# 3d_printer_timer.net
KiCad netlist of a schematic drawn in EAGLE
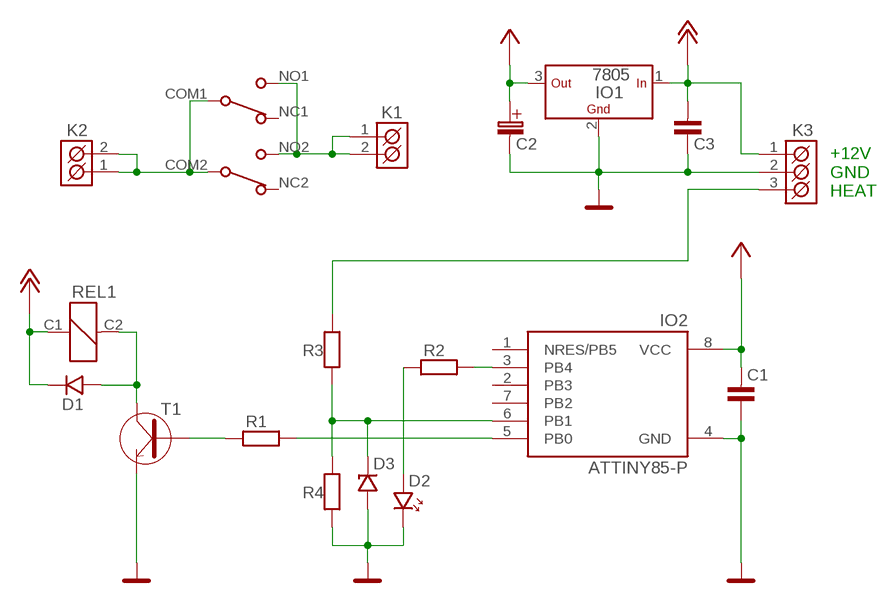
[diagram p0: schematic, sheet 1]

(export (version "E")
  (design (tool "Eeschema 10.0.6"))
  (components
    (comp (ref "C1")
      (value "100n")
      (footprint "eagle-import:1206")
      (libsource (lib "eagle-import") (part "C-KER_1206"))
    )
    (comp (ref "C2")
      (value "100u")
      (footprint "eagle-import:C-EL_2,5")
      (libsource (lib "eagle-import") (part "C-EL_2,5"))
    )
    (comp (ref "C3")
      (value "100n")
      (footprint "eagle-import:1206")
      (libsource (lib "eagle-import") (part "C-KER_1206"))
    )
    (comp (ref "D1")
      (value "1N4148")
      (footprint "eagle-import:DO35")
      (libsource (lib "eagle-import") (part "D_7,5"))
    )
    (comp (ref "D2")
      (value "LED_3")
      (footprint "eagle-import:LED_3")
      (libsource (lib "eagle-import") (part "LED_3"))
    )
    (comp (ref "D3")
      (value "5V1")
      (footprint "eagle-import:DO35")
      (libsource (lib "eagle-import") (part "D-?-ZENERBZX83V_0,5W"))
    )
    (comp (ref "IO1")
      (value "7805")
      (footprint "eagle-import:TO-220S")
      (libsource (lib "eagle-import") (part "78?_STO"))
    )
    (comp (ref "IO2")
      (value "ATTINY85-P")
      (footprint "eagle-import:PDIP08_300MIL")
      (libsource (lib "eagle-import") (part "ATTINY85P-"))
    )
    (comp (ref "K1")
      (value "ARK500/2")
      (footprint "eagle-import:ARK500_2")
      (libsource (lib "eagle-import") (part "ARK500/2"))
    )
    (comp (ref "K2")
      (value "ARK500/2")
      (footprint "eagle-import:ARK500_2")
      (libsource (lib "eagle-import") (part "ARK500/2"))
    )
    (comp (ref "K3")
      (value "ARK500/3")
      (footprint "eagle-import:ARK500_3")
      (libsource (lib "eagle-import") (part "ARK500/3"))
    )
    (comp (ref "R1")
      (value "1k")
      (footprint "eagle-import:R-10")
      (libsource (lib "eagle-import") (part "R_10"))
    )
    (comp (ref "R2")
      (value "330R")
      (footprint "eagle-import:R-10")
      (libsource (lib "eagle-import") (part "R_10"))
    )
    (comp (ref "R3")
      (value "R_10")
      (footprint "eagle-import:R-10")
      (libsource (lib "eagle-import") (part "R_10"))
    )
    (comp (ref "R4")
      (value "R_10")
      (footprint "eagle-import:R-10")
      (libsource (lib "eagle-import") (part "R_10"))
    )
    (comp (ref "REL1")
      (value "40.52")
      (footprint "eagle-import:RELEMZPA92")
      (libsource (lib "eagle-import") (part "RELEMZPA92"))
    )
    (comp (ref "T1")
      (value "BC546")
      (footprint "eagle-import:TO-92")
      (libsource (lib "eagle-import") (part "BC546"))
    )
  )
  (nets
    (net (code "1") (name "+5V") (class "Default")
      (node (ref "C1") (pin "2") (pinfunction "2_2") (pintype "passive"))
      (node (ref "C2") (pin "C+") (pinfunction "C_EL+_C+") (pintype "passive"))
      (node (ref "IO1") (pin "3") (pinfunction "OUT_3") (pintype "passive"))
      (node (ref "IO2") (pin "8") (pinfunction "VCC_8") (pintype "power_in"))
    )
    (net (code "2") (name "+12V") (class "Default")
      (node (ref "C3") (pin "2") (pinfunction "2_2") (pintype "passive"))
      (node (ref "D1") (pin "K") (pinfunction "K_K") (pintype "passive"))
      (node (ref "IO1") (pin "1") (pinfunction "IN_1") (pintype "passive"))
      (node (ref "K3") (pin "1") (pinfunction "K1_1") (pintype "passive"))
      (node (ref "REL1") (pin "C1") (pinfunction "C1_C1") (pintype "passive"))
    )
    (net (code "3") (name "GND") (class "Default")
      (node (ref "C1") (pin "1") (pinfunction "1_1") (pintype "passive"))
      (node (ref "C2") (pin "C-") (pinfunction "C_EL-_C-") (pintype "passive"))
      (node (ref "C3") (pin "1") (pinfunction "1_1") (pintype "passive"))
      (node (ref "D2") (pin "K") (pinfunction "K_K") (pintype "passive"))
      (node (ref "D3") (pin "A") (pinfunction "A_A") (pintype "passive"))
      (node (ref "IO1") (pin "2") (pinfunction "GND_2") (pintype "passive"))
      (node (ref "IO2") (pin "4") (pinfunction "GND_4") (pintype "power_in"))
      (node (ref "K3") (pin "2") (pinfunction "K2_2") (pintype "passive"))
      (node (ref "R4") (pin "1") (pinfunction "1_1") (pintype "passive"))
      (node (ref "T1") (pin "3") (pinfunction "E_3") (pintype "passive"))
    )
    (net (code "4") (name "Net-(D2-PadA)") (class "Default")
      (node (ref "D2") (pin "A") (pinfunction "A_A") (pintype "passive"))
      (node (ref "R2") (pin "1") (pinfunction "1_1") (pintype "passive"))
    )
    (net (code "5") (name "Net-(IO2-PB0)") (class "Default")
      (node (ref "IO2") (pin "5") (pinfunction "PB0_5") (pintype "bidirectional"))
      (node (ref "R1") (pin "2") (pinfunction "2_2") (pintype "passive"))
    )
    (net (code "6") (name "Net-(IO2-PB1)") (class "Default")
      (node (ref "D3") (pin "K") (pinfunction "K_K") (pintype "passive"))
      (node (ref "IO2") (pin "6") (pinfunction "PB1_6") (pintype "bidirectional"))
      (node (ref "R3") (pin "1") (pinfunction "1_1") (pintype "passive"))
      (node (ref "R4") (pin "2") (pinfunction "2_2") (pintype "passive"))
    )
    (net (code "7") (name "Net-(IO2-PB4)") (class "Default")
      (node (ref "IO2") (pin "3") (pinfunction "PB4_3") (pintype "bidirectional"))
      (node (ref "R2") (pin "2") (pinfunction "2_2") (pintype "passive"))
    )
    (net (code "8") (name "Net-(K1-K1)") (class "Default")
      (node (ref "K1") (pin "1") (pinfunction "K1_1") (pintype "passive"))
      (node (ref "K1") (pin "2") (pinfunction "K2_2") (pintype "passive"))
      (node (ref "REL1") (pin "NO1") (pinfunction "NO_NO1") (pintype "passive"))
      (node (ref "REL1") (pin "NO2") (pinfunction "NO_NO2") (pintype "passive"))
    )
    (net (code "9") (name "Net-(K2-K1)") (class "Default")
      (node (ref "K2") (pin "1") (pinfunction "K1_1") (pintype "passive"))
      (node (ref "K2") (pin "2") (pinfunction "K2_2") (pintype "passive"))
      (node (ref "REL1") (pin "COM1") (pinfunction "COM_COM1") (pintype "passive"))
      (node (ref "REL1") (pin "COM2") (pinfunction "COM_COM2") (pintype "passive"))
    )
    (net (code "10") (name "Net-(K3-K3)") (class "Default")
      (node (ref "K3") (pin "3") (pinfunction "K3_3") (pintype "passive"))
      (node (ref "R3") (pin "2") (pinfunction "2_2") (pintype "passive"))
    )
    (net (code "11") (name "Net-(T1-B)") (class "Default")
      (node (ref "R1") (pin "1") (pinfunction "1_1") (pintype "passive"))
      (node (ref "T1") (pin "2") (pinfunction "B_2") (pintype "passive"))
    )
    (net (code "12") (name "Net-(T1-C)") (class "Default")
      (node (ref "D1") (pin "A") (pinfunction "A_A") (pintype "passive"))
      (node (ref "REL1") (pin "C2") (pinfunction "C2_C2") (pintype "passive"))
      (node (ref "T1") (pin "1") (pinfunction "C_1") (pintype "passive"))
    )
    (net (code "13") (name "unconnected-(IO2-NRES{slash}PB5-Pad1)") (class "Default")
      (node (ref "IO2") (pin "1") (pinfunction "NRES/PB5_1") (pintype "bidirectional"))
    )
    (net (code "14") (name "unconnected-(IO2-PB2-Pad7)") (class "Default")
      (node (ref "IO2") (pin "7") (pinfunction "PB2_7") (pintype "bidirectional"))
    )
    (net (code "15") (name "unconnected-(IO2-PB3-Pad2)") (class "Default")
      (node (ref "IO2") (pin "2") (pinfunction "PB3_2") (pintype "bidirectional"))
    )
    (net (code "16") (name "unconnected-(REL1B-NC-PadNC1)") (class "Default")
      (node (ref "REL1") (pin "NC1") (pinfunction "NC_NC1") (pintype "passive"))
    )
    (net (code "17") (name "unconnected-(REL1C-NC-PadNC2)") (class "Default")
      (node (ref "REL1") (pin "NC2") (pinfunction "NC_NC2") (pintype "passive"))
    )
  )
)
